# Components_wheatherlab.net
KiCad netlist of a schematic drawn in Altium Designer
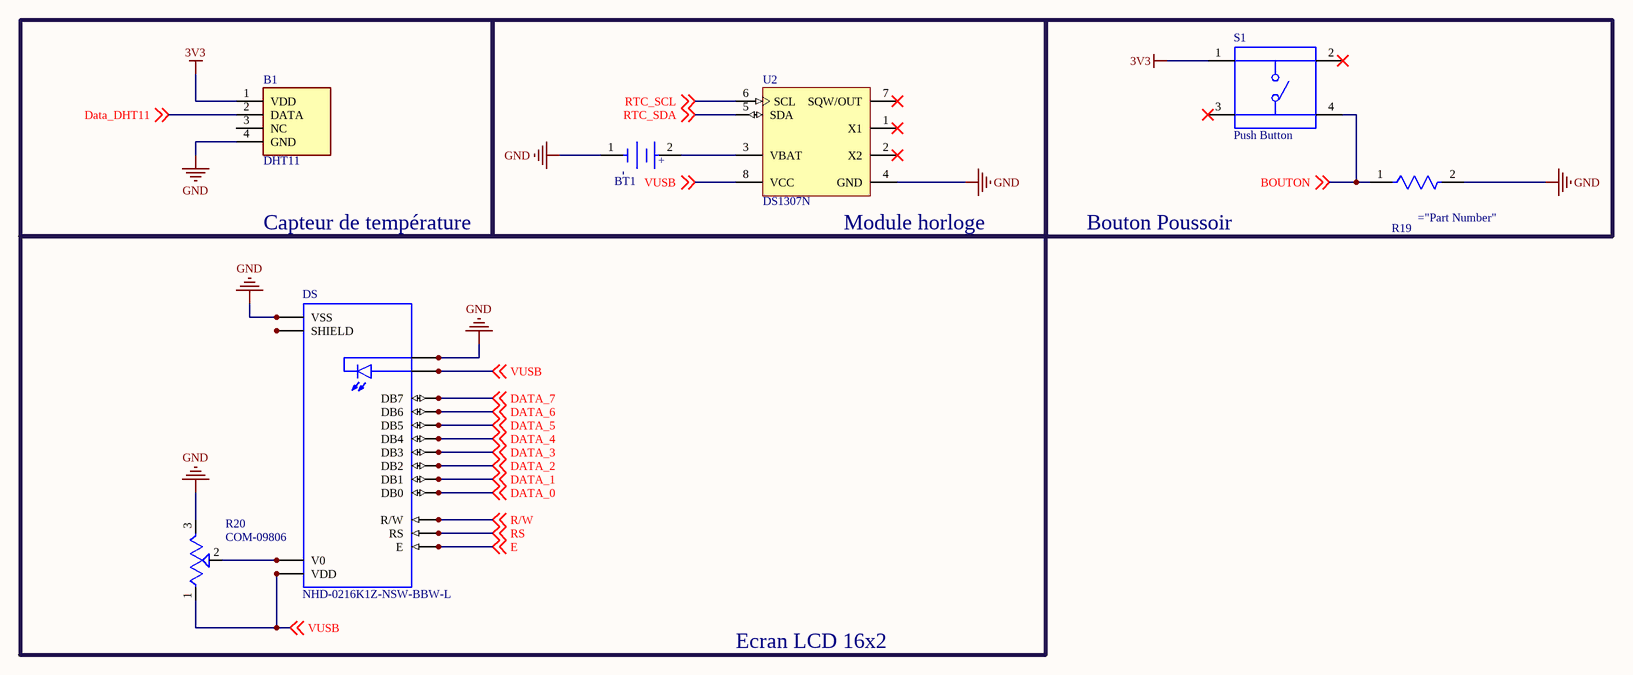
[diagram p0: Components_wheatherlab.SchDoc]

(export (version "E")
  (design (tool "Eeschema 10.0.6"))
  (components
    (comp (ref "B1")
      (value "DHT11")
      (footprint "386")
      (description "Adafruit Accessories DHT11 Basic Temp Humidity Sensor")
      (fields (field (name "MANUFACTURER_PART_NUMBER") "386") (field (name "MOUSER PART NUMBER") "485-386"))
      (libsource (lib "386") (part "386"))
    )
    (comp (ref "BT1")
      (value "3034TR")
      (footprint "Keystone_0_MFG")
      (libsource (lib "Batt_Keystone_3034TR_eec") (part "3034TR"))
    )
    (comp (ref "DS")
      (value "NHD-0216K1Z-NSW-BBW-L")
      (footprint "NHD_NHD-0216K1Z-NSW-BBW-L")
      (fields
        (field (name "MF") "Newhaven Display")
        (field (name "DIGI-KEY_PART_NUMBER") "NHD-0216K1Z-NSW-BBW-L-ND")
      )
      (libsource (lib "NHD-0216K1Z-NSW-BBW-L") (part "NHD-0216K1Z-NSW-BBW-L"))
    )
    (comp (ref "R19")
      (value "10kohm")
      (footprint "Stackpole_RMCF0603_IPC_A")
      (libsource (lib "Res_Stackpole_RMCF0603FT220R_eec") (part "RMCF0603FT220R"))
    )
    (comp (ref "R20")
      (value "COM-09806")
      (footprint "TRIM_COM-09806")
      (description "10 kOhms 0.5W, 1/2W PC Pins Through Hole Trimmer Potentiometer Cermet 1 Turn Top Adjustment")
      (libsource (lib "COM-09806") (part "COM-09806"))
    )
    (comp (ref "S1")
      (value "Push Button")
      (footprint "SW_TS02-66-50-BK-160-LCR-D")
      (fields (field (name "MF") "{'manufacturer': u'CUI'}") (field (name "MP") "TS02-66-50-BK-160-LCR-D"))
      (libsource (lib "TS02-66-50-BK-160-LCR-D") (part "TS02-66-50-BK-160-LCR-D"))
    )
    (comp (ref "U2")
      (value "DS1307N")
      (footprint "P8-2")
      (description "64 x 8, Serial, I2C Real-Time Clock, 5.0V, 8-Pin PDIP, -40 to 85 degC")
      (libsource (lib "Maxim_DS1307N") (part "DS1307N"))
    )
  )
  (nets
    (net (code "1") (name "3V3") (class "Default")
      (node (ref "B1") (pin "1") (pinfunction "VDD_1") (pintype "passive"))
      (node (ref "S1") (pin "1") (pinfunction "1_1") (pintype "passive"))
    )
    (net (code "2") (name "BOUTON") (class "Default")
      (node (ref "R19") (pin "1") (pinfunction "1_1") (pintype "passive"))
      (node (ref "S1") (pin "4") (pinfunction "4_4") (pintype "passive"))
    )
    (net (code "3") (name "DATA_0") (class "Default")
      (node (ref "DS") (pin "7_1") (pinfunction "DB0_7_1") (pintype "bidirectional"))
      (node (ref "DS") (pin "7_2") (pinfunction "DB0_7_2") (pintype "bidirectional"))
    )
    (net (code "4") (name "DATA_1") (class "Default")
      (node (ref "DS") (pin "8_1") (pinfunction "DB1_8_1") (pintype "bidirectional"))
      (node (ref "DS") (pin "8_2") (pinfunction "DB1_8_2") (pintype "bidirectional"))
    )
    (net (code "5") (name "DATA_2") (class "Default")
      (node (ref "DS") (pin "9_1") (pinfunction "DB2_9_1") (pintype "bidirectional"))
      (node (ref "DS") (pin "9_2") (pinfunction "DB2_9_2") (pintype "bidirectional"))
    )
    (net (code "6") (name "DATA_3") (class "Default")
      (node (ref "DS") (pin "10_1") (pinfunction "DB3_10_1") (pintype "bidirectional"))
      (node (ref "DS") (pin "10_2") (pinfunction "DB3_10_2") (pintype "bidirectional"))
    )
    (net (code "7") (name "DATA_4") (class "Default")
      (node (ref "DS") (pin "11_1") (pinfunction "DB4_11_1") (pintype "bidirectional"))
      (node (ref "DS") (pin "11_2") (pinfunction "DB4_11_2") (pintype "bidirectional"))
    )
    (net (code "8") (name "DATA_5") (class "Default")
      (node (ref "DS") (pin "12_1") (pinfunction "DB5_12_1") (pintype "bidirectional"))
      (node (ref "DS") (pin "12_2") (pinfunction "DB5_12_2") (pintype "bidirectional"))
    )
    (net (code "9") (name "DATA_6") (class "Default")
      (node (ref "DS") (pin "13_1") (pinfunction "DB6_13_1") (pintype "bidirectional"))
      (node (ref "DS") (pin "13_2") (pinfunction "DB6_13_2") (pintype "bidirectional"))
    )
    (net (code "10") (name "DATA_7") (class "Default")
      (node (ref "DS") (pin "14_1") (pinfunction "DB7_14_1") (pintype "bidirectional"))
      (node (ref "DS") (pin "14_2") (pinfunction "DB7_14_2") (pintype "bidirectional"))
    )
    (net (code "11") (name "Data_DHT11") (class "Default")
      (node (ref "B1") (pin "2") (pinfunction "DATA_2") (pintype "passive"))
    )
    (net (code "12") (name "E") (class "Default")
      (node (ref "DS") (pin "6_1") (pinfunction "E_6_1") (pintype "input"))
      (node (ref "DS") (pin "6_2") (pinfunction "E_6_2") (pintype "input"))
    )
    (net (code "13") (name "GND") (class "Default")
      (node (ref "B1") (pin "4") (pinfunction "GND_4") (pintype "passive"))
      (node (ref "BT1") (pin "1") (pinfunction "C_1") (pintype "passive"))
      (node (ref "DS") (pin "16_1") (pinfunction "LED-_16_1") (pintype "passive"))
      (node (ref "DS") (pin "16_2") (pinfunction "LED-_16_2") (pintype "passive"))
      (node (ref "DS") (pin "1_1") (pinfunction "VSS_1_1") (pintype "power_in"))
      (node (ref "DS") (pin "1_2") (pinfunction "VSS_1_2") (pintype "power_in"))
      (node (ref "R19") (pin "2") (pinfunction "2_2") (pintype "passive"))
      (node (ref "R20") (pin "3") (pinfunction "CW_3") (pintype "passive"))
      (node (ref "U2") (pin "4") (pinfunction "GND_4") (pintype "power_in"))
    )
    (net (code "14") (name "Net-(BT1-A)") (class "Default")
      (node (ref "BT1") (pin "2") (pinfunction "A_2") (pintype "passive"))
      (node (ref "U2") (pin "3") (pinfunction "VBAT_3") (pintype "power_in"))
    )
    (net (code "15") (name "Net-(DS-SHIELD-PadS1)") (class "Default")
      (node (ref "DS") (pin "S1") (pinfunction "SHIELD_S1") (pintype "passive"))
      (node (ref "DS") (pin "S2") (pinfunction "SHIELD_S2") (pintype "passive"))
      (node (ref "DS") (pin "S3") (pinfunction "SHIELD_S3") (pintype "passive"))
      (node (ref "DS") (pin "S4") (pinfunction "SHIELD_S4") (pintype "passive"))
    )
    (net (code "16") (name "Net-(R20-WIPER)") (class "Default")
      (node (ref "DS") (pin "3_1") (pinfunction "V0_3_1") (pintype "power_in"))
      (node (ref "DS") (pin "3_2") (pinfunction "V0_3_2") (pintype "power_in"))
      (node (ref "R20") (pin "2") (pinfunction "WIPER_2") (pintype "passive"))
    )
    (net (code "17") (name "RS") (class "Default")
      (node (ref "DS") (pin "4_1") (pinfunction "RS_4_1") (pintype "input"))
      (node (ref "DS") (pin "4_2") (pinfunction "RS_4_2") (pintype "input"))
    )
    (net (code "18") (name "RTC_SCL") (class "Default")
      (node (ref "U2") (pin "6") (pinfunction "SCL_6") (pintype "input"))
    )
    (net (code "19") (name "RTC_SDA") (class "Default")
      (node (ref "U2") (pin "5") (pinfunction "SDA_5") (pintype "bidirectional"))
    )
    (net (code "20") (name "R{slash}W") (class "Default")
      (node (ref "DS") (pin "5_1") (pinfunction "R/W_5_1") (pintype "input"))
      (node (ref "DS") (pin "5_2") (pinfunction "R/W_5_2") (pintype "input"))
    )
    (net (code "21") (name "VUSB") (class "Default")
      (node (ref "DS") (pin "15_1") (pinfunction "LED+_15_1") (pintype "passive"))
      (node (ref "DS") (pin "15_2") (pinfunction "LED+_15_2") (pintype "passive"))
      (node (ref "DS") (pin "2_1") (pinfunction "VDD_2_1") (pintype "power_in"))
      (node (ref "DS") (pin "2_2") (pinfunction "VDD_2_2") (pintype "power_in"))
      (node (ref "R20") (pin "1") (pinfunction "CCW_1") (pintype "passive"))
      (node (ref "U2") (pin "8") (pinfunction "VCC_8") (pintype "power_in"))
    )
    (net (code "22") (name "unconnected-(B1-NC-Pad3)") (class "Default")
      (node (ref "B1") (pin "3") (pinfunction "NC_3") (pintype "passive"))
    )
    (net (code "23") (name "unconnected-(S1-Pad2)") (class "Default")
      (node (ref "S1") (pin "2") (pinfunction "2_2") (pintype "passive+no_connect"))
    )
    (net (code "24") (name "unconnected-(S1-Pad3)") (class "Default")
      (node (ref "S1") (pin "3") (pinfunction "3_3") (pintype "passive+no_connect"))
    )
    (net (code "25") (name "unconnected-(U2-SQW{slash}OUT-Pad7)") (class "Default")
      (node (ref "U2") (pin "7") (pinfunction "SQW/OUT_7") (pintype "open_collector+no_connect"))
    )
    (net (code "26") (name "unconnected-(U2-X1-Pad1)") (class "Default")
      (node (ref "U2") (pin "1") (pinfunction "X1_1") (pintype "passive+no_connect"))
    )
    (net (code "27") (name "unconnected-(U2-X2-Pad2)") (class "Default")
      (node (ref "U2") (pin "2") (pinfunction "X2_2") (pintype "passive+no_connect"))
    )
  )
)
